# ZeroESPminimal.net
KiCad netlist of a schematic drawn in EAGLE
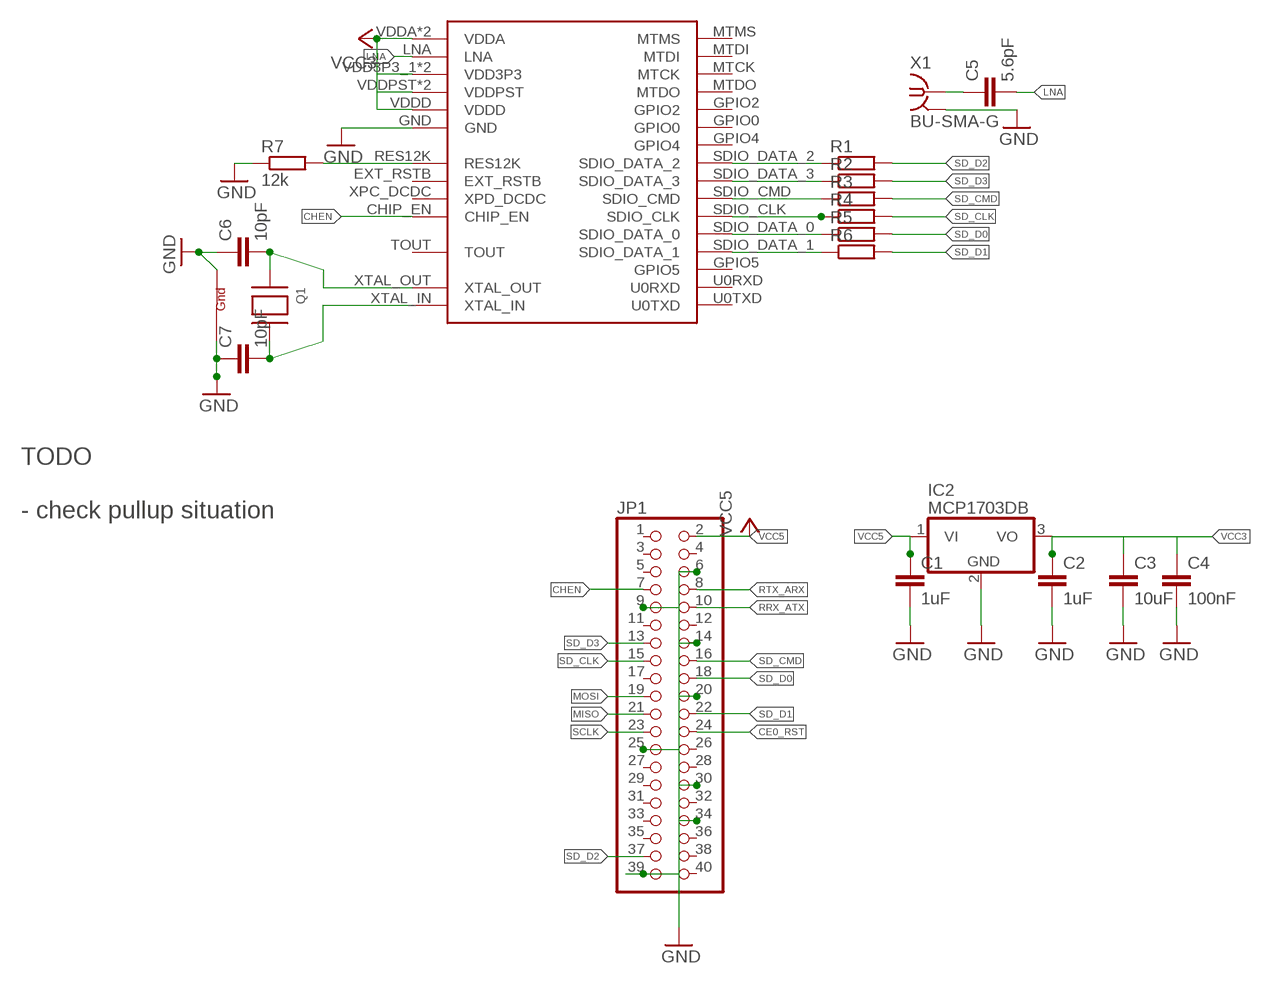
[diagram p0: schematic, sheet 1]

(export (version "E")
  (design (tool "Eeschema 10.0.6"))
  (components
    (comp (ref "C1")
      (value "1uF")
      (footprint "eagle-import:C1206")
      (libsource (lib "eagle-import") (part "C-EUC1206"))
    )
    (comp (ref "C2")
      (value "1uF")
      (footprint "eagle-import:C1206")
      (libsource (lib "eagle-import") (part "C-EUC1206"))
    )
    (comp (ref "C3")
      (value "10uF")
      (footprint "eagle-import:C1206")
      (libsource (lib "eagle-import") (part "C-EUC1206"))
    )
    (comp (ref "C4")
      (value "100nF")
      (footprint "eagle-import:C1206")
      (libsource (lib "eagle-import") (part "C-EUC1206"))
    )
    (comp (ref "C5")
      (value "5.6pF")
      (footprint "eagle-import:C0402")
      (libsource (lib "eagle-import") (part "resistor_C-EUC0402"))
    )
    (comp (ref "C6")
      (value "10pF")
      (footprint "eagle-import:C0402")
      (libsource (lib "eagle-import") (part "resistor_C-EUC0402"))
    )
    (comp (ref "C7")
      (value "10pF")
      (footprint "eagle-import:C0402")
      (libsource (lib "eagle-import") (part "resistor_C-EUC0402"))
    )
    (comp (ref "IC2")
      (value "MCP1703DB")
      (footprint "eagle-import:SOT223")
      (libsource (lib "eagle-import") (part "MCP1703DB"))
    )
    (comp (ref "JP1")
      (value "PINHD-2X20")
      (footprint "eagle-import:2X20")
      (libsource (lib "eagle-import") (part "PINHD-2X20"))
    )
    (comp (ref "Q1")
      (value "XTAL-4-3225")
      (footprint "eagle-import:NX3225")
      (libsource (lib "eagle-import") (part "XTAL-4-3225"))
    )
    (comp (ref "R1")
      (value "R-EU_R0402")
      (footprint "eagle-import:R0402")
      (libsource (lib "eagle-import") (part "R-EU_R0402"))
    )
    (comp (ref "R2")
      (value "R-EU_R0402")
      (footprint "eagle-import:R0402")
      (libsource (lib "eagle-import") (part "R-EU_R0402"))
    )
    (comp (ref "R3")
      (value "R-EU_R0402")
      (footprint "eagle-import:R0402")
      (libsource (lib "eagle-import") (part "R-EU_R0402"))
    )
    (comp (ref "R4")
      (value "R-EU_R0402")
      (footprint "eagle-import:R0402")
      (libsource (lib "eagle-import") (part "R-EU_R0402"))
    )
    (comp (ref "R5")
      (value "R-EU_R0402")
      (footprint "eagle-import:R0402")
      (libsource (lib "eagle-import") (part "R-EU_R0402"))
    )
    (comp (ref "R6")
      (value "R-EU_R0402")
      (footprint "eagle-import:R0402")
      (libsource (lib "eagle-import") (part "R-EU_R0402"))
    )
    (comp (ref "R7")
      (value "12k")
      (footprint "eagle-import:R0402")
      (libsource (lib "eagle-import") (part "resistor_R-EU_R0402"))
    )
    (comp (ref "U$3")
      (value "ESP8266EX")
      (footprint "eagle-import:ESP8266EX")
      (libsource (lib "eagle-import") (part "ESP8266EX"))
    )
    (comp (ref "X1")
      (value "BU-SMA-G")
      (footprint "eagle-import:BU-SMA-G")
      (libsource (lib "eagle-import") (part "BU-SMA-G"))
    )
  )
  (nets
    (net (code "1") (name "CE0_RST") (class "Default")
      (node (ref "JP1") (pin "24") (pinfunction "24_24") (pintype "passive"))
    )
    (net (code "2") (name "CHEN") (class "Default")
      (node (ref "JP1") (pin "7") (pinfunction "7_7") (pintype "passive"))
      (node (ref "U$3") (pin "CHIP_EN") (pinfunction "CHIP_EN_CHIP_EN") (pintype "bidirectional"))
    )
    (net (code "3") (name "GND") (class "Default")
      (node (ref "C1") (pin "2") (pinfunction "2_2") (pintype "passive"))
      (node (ref "C2") (pin "2") (pinfunction "2_2") (pintype "passive"))
      (node (ref "C3") (pin "2") (pinfunction "2_2") (pintype "passive"))
      (node (ref "C4") (pin "2") (pinfunction "2_2") (pintype "passive"))
      (node (ref "C6") (pin "1") (pinfunction "1_1") (pintype "passive"))
      (node (ref "C7") (pin "1") (pinfunction "1_1") (pintype "passive"))
      (node (ref "IC2") (pin "2") (pinfunction "GND_2") (pintype "passive"))
      (node (ref "JP1") (pin "14") (pinfunction "14_14") (pintype "passive"))
      (node (ref "JP1") (pin "20") (pinfunction "20_20") (pintype "passive"))
      (node (ref "JP1") (pin "25") (pinfunction "25_25") (pintype "passive"))
      (node (ref "JP1") (pin "30") (pinfunction "30_30") (pintype "passive"))
      (node (ref "JP1") (pin "34") (pinfunction "34_34") (pintype "passive"))
      (node (ref "JP1") (pin "39") (pinfunction "39_39") (pintype "passive"))
      (node (ref "JP1") (pin "6") (pinfunction "6_6") (pintype "passive"))
      (node (ref "JP1") (pin "9") (pinfunction "9_9") (pintype "passive"))
      (node (ref "Q1") (pin "2") (pinfunction "G2_2") (pintype "power_in"))
      (node (ref "Q1") (pin "4") (pinfunction "G1_4") (pintype "power_in"))
      (node (ref "R7") (pin "1") (pinfunction "1_1") (pintype "passive"))
      (node (ref "U$3") (pin "GND") (pinfunction "GND_GND") (pintype "bidirectional"))
      (node (ref "X1") (pin "2") (pinfunction "2_2") (pintype "passive"))
      (node (ref "X1") (pin "3") (pinfunction "2_3") (pintype "passive"))
      (node (ref "X1") (pin "4") (pinfunction "2_4") (pintype "passive"))
      (node (ref "X1") (pin "5") (pinfunction "2_5") (pintype "passive"))
    )
    (net (code "4") (name "LNA") (class "Default")
      (node (ref "C5") (pin "2") (pinfunction "2_2") (pintype "passive"))
      (node (ref "U$3") (pin "LNA") (pinfunction "LNA_LNA") (pintype "bidirectional"))
    )
    (net (code "5") (name "MISO") (class "Default")
      (node (ref "JP1") (pin "21") (pinfunction "21_21") (pintype "passive"))
    )
    (net (code "6") (name "MOSI") (class "Default")
      (node (ref "JP1") (pin "19") (pinfunction "19_19") (pintype "passive"))
    )
    (net (code "7") (name "Net-(C5-Pad1)") (class "Default")
      (node (ref "C5") (pin "1") (pinfunction "1_1") (pintype "passive"))
      (node (ref "X1") (pin "1") (pinfunction "1_1") (pintype "passive"))
    )
    (net (code "8") (name "Net-(Q1-X1)") (class "Default")
      (node (ref "C6") (pin "2") (pinfunction "2_2") (pintype "passive"))
      (node (ref "Q1") (pin "1") (pinfunction "X1_1") (pintype "bidirectional"))
      (node (ref "U$3") (pin "XTAL_OUT") (pinfunction "XTAL_OUT_XTAL_OUT") (pintype "bidirectional"))
    )
    (net (code "9") (name "Net-(Q1-X2)") (class "Default")
      (node (ref "C7") (pin "2") (pinfunction "2_2") (pintype "passive"))
      (node (ref "Q1") (pin "3") (pinfunction "X2_3") (pintype "bidirectional"))
      (node (ref "U$3") (pin "XTAL_IN") (pinfunction "XTAL_IN_XTAL_IN") (pintype "bidirectional"))
    )
    (net (code "10") (name "Net-(R1-Pad1)") (class "Default")
      (node (ref "R1") (pin "1") (pinfunction "1_1") (pintype "passive"))
      (node (ref "U$3") (pin "SDIO_DATA_2") (pinfunction "SDIO_DATA_2_SDIO_DATA_2") (pintype "bidirectional"))
    )
    (net (code "11") (name "Net-(R2-Pad1)") (class "Default")
      (node (ref "R2") (pin "1") (pinfunction "1_1") (pintype "passive"))
      (node (ref "U$3") (pin "SDIO_DATA_3") (pinfunction "SDIO_DATA_3_SDIO_DATA_3") (pintype "bidirectional"))
    )
    (net (code "12") (name "Net-(R3-Pad1)") (class "Default")
      (node (ref "R3") (pin "1") (pinfunction "1_1") (pintype "passive"))
      (node (ref "U$3") (pin "SDIO_CMD") (pinfunction "SDIO_CMD_SDIO_CMD") (pintype "bidirectional"))
    )
    (net (code "13") (name "Net-(R4-Pad1)") (class "Default")
      (node (ref "R4") (pin "1") (pinfunction "1_1") (pintype "passive"))
      (node (ref "U$3") (pin "SDIO_CLK") (pinfunction "SDIO_CLK_SDIO_CLK") (pintype "bidirectional"))
    )
    (net (code "14") (name "Net-(R5-Pad1)") (class "Default")
      (node (ref "R5") (pin "1") (pinfunction "1_1") (pintype "passive"))
      (node (ref "U$3") (pin "SDIO_DATA_0") (pinfunction "SDIO_DATA_0_SDIO_DATA_0") (pintype "bidirectional"))
    )
    (net (code "15") (name "Net-(R6-Pad1)") (class "Default")
      (node (ref "R6") (pin "1") (pinfunction "1_1") (pintype "passive"))
      (node (ref "U$3") (pin "SDIO_DATA_1") (pinfunction "SDIO_DATA_1_SDIO_DATA_1") (pintype "bidirectional"))
    )
    (net (code "16") (name "Net-(R7-Pad2)") (class "Default")
      (node (ref "R7") (pin "2") (pinfunction "2_2") (pintype "passive"))
      (node (ref "U$3") (pin "RES12K") (pinfunction "RES12K_RES12K") (pintype "bidirectional"))
    )
    (net (code "17") (name "RRX_ATX") (class "Default")
      (node (ref "JP1") (pin "10") (pinfunction "10_10") (pintype "passive"))
    )
    (net (code "18") (name "RTX_ARX") (class "Default")
      (node (ref "JP1") (pin "8") (pinfunction "8_8") (pintype "passive"))
    )
    (net (code "19") (name "SCLK") (class "Default")
      (node (ref "JP1") (pin "23") (pinfunction "23_23") (pintype "passive"))
    )
    (net (code "20") (name "SD_CLK") (class "Default")
      (node (ref "JP1") (pin "15") (pinfunction "15_15") (pintype "passive"))
      (node (ref "R4") (pin "2") (pinfunction "2_2") (pintype "passive"))
    )
    (net (code "21") (name "SD_CMD") (class "Default")
      (node (ref "JP1") (pin "16") (pinfunction "16_16") (pintype "passive"))
      (node (ref "R3") (pin "2") (pinfunction "2_2") (pintype "passive"))
    )
    (net (code "22") (name "SD_D0") (class "Default")
      (node (ref "JP1") (pin "18") (pinfunction "18_18") (pintype "passive"))
      (node (ref "R5") (pin "2") (pinfunction "2_2") (pintype "passive"))
    )
    (net (code "23") (name "SD_D1") (class "Default")
      (node (ref "JP1") (pin "22") (pinfunction "22_22") (pintype "passive"))
      (node (ref "R6") (pin "2") (pinfunction "2_2") (pintype "passive"))
    )
    (net (code "24") (name "SD_D2") (class "Default")
      (node (ref "JP1") (pin "37") (pinfunction "37_37") (pintype "passive"))
      (node (ref "R1") (pin "2") (pinfunction "2_2") (pintype "passive"))
    )
    (net (code "25") (name "SD_D3") (class "Default")
      (node (ref "JP1") (pin "13") (pinfunction "13_13") (pintype "passive"))
      (node (ref "R2") (pin "2") (pinfunction "2_2") (pintype "passive"))
    )
    (net (code "26") (name "VCC3") (class "Default")
      (node (ref "C2") (pin "1") (pinfunction "1_1") (pintype "passive"))
      (node (ref "C3") (pin "1") (pinfunction "1_1") (pintype "passive"))
      (node (ref "C4") (pin "1") (pinfunction "1_1") (pintype "passive"))
      (node (ref "IC2") (pin "3") (pinfunction "VO_3") (pintype "passive"))
      (node (ref "U$3") (pin "VDD3P3_1") (pinfunction "VDD3P3_VDD3P3_1") (pintype "bidirectional"))
      (node (ref "U$3") (pin "VDD3P3_2") (pinfunction "VDD3P3_VDD3P3_2") (pintype "bidirectional"))
      (node (ref "U$3") (pin "VDDA") (pinfunction "VDDA_VDDA") (pintype "bidirectional"))
      (node (ref "U$3") (pin "VDDA_2") (pinfunction "VDDA_VDDA_2") (pintype "bidirectional"))
      (node (ref "U$3") (pin "VDDD") (pinfunction "VDDD_VDDD") (pintype "bidirectional"))
      (node (ref "U$3") (pin "VDDPST") (pinfunction "VDDPST_VDDPST") (pintype "bidirectional"))
      (node (ref "U$3") (pin "VDDPST_2") (pinfunction "VDDPST_VDDPST_2") (pintype "bidirectional"))
    )
    (net (code "27") (name "VCC5") (class "Default")
      (node (ref "C1") (pin "1") (pinfunction "1_1") (pintype "passive"))
      (node (ref "IC2") (pin "1") (pinfunction "VI_1") (pintype "input"))
      (node (ref "JP1") (pin "2") (pinfunction "2_2") (pintype "passive"))
    )
    (net (code "28") (name "unconnected-(JP1-Pad1)") (class "Default")
      (node (ref "JP1") (pin "1") (pinfunction "1_1") (pintype "passive"))
    )
    (net (code "29") (name "unconnected-(JP1-Pad3)") (class "Default")
      (node (ref "JP1") (pin "3") (pinfunction "3_3") (pintype "passive"))
    )
    (net (code "30") (name "unconnected-(JP1-Pad4)") (class "Default")
      (node (ref "JP1") (pin "4") (pinfunction "4_4") (pintype "passive"))
    )
    (net (code "31") (name "unconnected-(JP1-Pad5)") (class "Default")
      (node (ref "JP1") (pin "5") (pinfunction "5_5") (pintype "passive"))
    )
    (net (code "32") (name "unconnected-(JP1-Pad11)") (class "Default")
      (node (ref "JP1") (pin "11") (pinfunction "11_11") (pintype "passive"))
    )
    (net (code "33") (name "unconnected-(JP1-Pad12)") (class "Default")
      (node (ref "JP1") (pin "12") (pinfunction "12_12") (pintype "passive"))
    )
    (net (code "34") (name "unconnected-(JP1-Pad17)") (class "Default")
      (node (ref "JP1") (pin "17") (pinfunction "17_17") (pintype "passive"))
    )
    (net (code "35") (name "unconnected-(JP1-Pad26)") (class "Default")
      (node (ref "JP1") (pin "26") (pinfunction "26_26") (pintype "passive"))
    )
    (net (code "36") (name "unconnected-(JP1-Pad27)") (class "Default")
      (node (ref "JP1") (pin "27") (pinfunction "27_27") (pintype "passive"))
    )
    (net (code "37") (name "unconnected-(JP1-Pad28)") (class "Default")
      (node (ref "JP1") (pin "28") (pinfunction "28_28") (pintype "passive"))
    )
    (net (code "38") (name "unconnected-(JP1-Pad29)") (class "Default")
      (node (ref "JP1") (pin "29") (pinfunction "29_29") (pintype "passive"))
    )
    (net (code "39") (name "unconnected-(JP1-Pad31)") (class "Default")
      (node (ref "JP1") (pin "31") (pinfunction "31_31") (pintype "passive"))
    )
    (net (code "40") (name "unconnected-(JP1-Pad32)") (class "Default")
      (node (ref "JP1") (pin "32") (pinfunction "32_32") (pintype "passive"))
    )
    (net (code "41") (name "unconnected-(JP1-Pad33)") (class "Default")
      (node (ref "JP1") (pin "33") (pinfunction "33_33") (pintype "passive"))
    )
    (net (code "42") (name "unconnected-(JP1-Pad35)") (class "Default")
      (node (ref "JP1") (pin "35") (pinfunction "35_35") (pintype "passive"))
    )
    (net (code "43") (name "unconnected-(JP1-Pad36)") (class "Default")
      (node (ref "JP1") (pin "36") (pinfunction "36_36") (pintype "passive"))
    )
    (net (code "44") (name "unconnected-(JP1-Pad38)") (class "Default")
      (node (ref "JP1") (pin "38") (pinfunction "38_38") (pintype "passive"))
    )
    (net (code "45") (name "unconnected-(JP1-Pad40)") (class "Default")
      (node (ref "JP1") (pin "40") (pinfunction "40_40") (pintype "passive"))
    )
    (net (code "46") (name "unconnected-(U$3-PadEXT_RSTB)") (class "Default")
      (node (ref "U$3") (pin "EXT_RSTB") (pinfunction "EXT_RSTB_EXT_RSTB") (pintype "bidirectional"))
    )
    (net (code "47") (name "unconnected-(U$3-PadGPIO0)") (class "Default")
      (node (ref "U$3") (pin "GPIO0") (pinfunction "GPIO0_GPIO0") (pintype "bidirectional"))
    )
    (net (code "48") (name "unconnected-(U$3-PadGPIO2)") (class "Default")
      (node (ref "U$3") (pin "GPIO2") (pinfunction "GPIO2_GPIO2") (pintype "bidirectional"))
    )
    (net (code "49") (name "unconnected-(U$3-PadGPIO4)") (class "Default")
      (node (ref "U$3") (pin "GPIO4") (pinfunction "GPIO4_GPIO4") (pintype "bidirectional"))
    )
    (net (code "50") (name "unconnected-(U$3-PadGPIO5)") (class "Default")
      (node (ref "U$3") (pin "GPIO5") (pinfunction "GPIO5_GPIO5") (pintype "bidirectional"))
    )
    (net (code "51") (name "unconnected-(U$3-PadMTCK)") (class "Default")
      (node (ref "U$3") (pin "MTCK") (pinfunction "MTCK_MTCK") (pintype "bidirectional"))
    )
    (net (code "52") (name "unconnected-(U$3-PadMTDI)") (class "Default")
      (node (ref "U$3") (pin "MTDI") (pinfunction "MTDI_MTDI") (pintype "bidirectional"))
    )
    (net (code "53") (name "unconnected-(U$3-PadMTDO)") (class "Default")
      (node (ref "U$3") (pin "MTDO") (pinfunction "MTDO_MTDO") (pintype "bidirectional"))
    )
    (net (code "54") (name "unconnected-(U$3-PadMTMS)") (class "Default")
      (node (ref "U$3") (pin "MTMS") (pinfunction "MTMS_MTMS") (pintype "bidirectional"))
    )
    (net (code "55") (name "unconnected-(U$3-PadTOUT)") (class "Default")
      (node (ref "U$3") (pin "TOUT") (pinfunction "TOUT_TOUT") (pintype "bidirectional"))
    )
    (net (code "56") (name "unconnected-(U$3-PadU0RXD)") (class "Default")
      (node (ref "U$3") (pin "U0RXD") (pinfunction "U0RXD_U0RXD") (pintype "bidirectional"))
    )
    (net (code "57") (name "unconnected-(U$3-PadU0TXD)") (class "Default")
      (node (ref "U$3") (pin "U0TXD") (pinfunction "U0TXD_U0TXD") (pintype "bidirectional"))
    )
    (net (code "58") (name "unconnected-(U$3-XPD_DCDC-PadXPC_DCDC)") (class "Default")
      (node (ref "U$3") (pin "XPC_DCDC") (pinfunction "XPD_DCDC_XPC_DCDC") (pintype "bidirectional"))
    )
  )
)
